# Nu_Multi_Output_Board.net
KiCad netlist of a schematic drawn in EAGLE
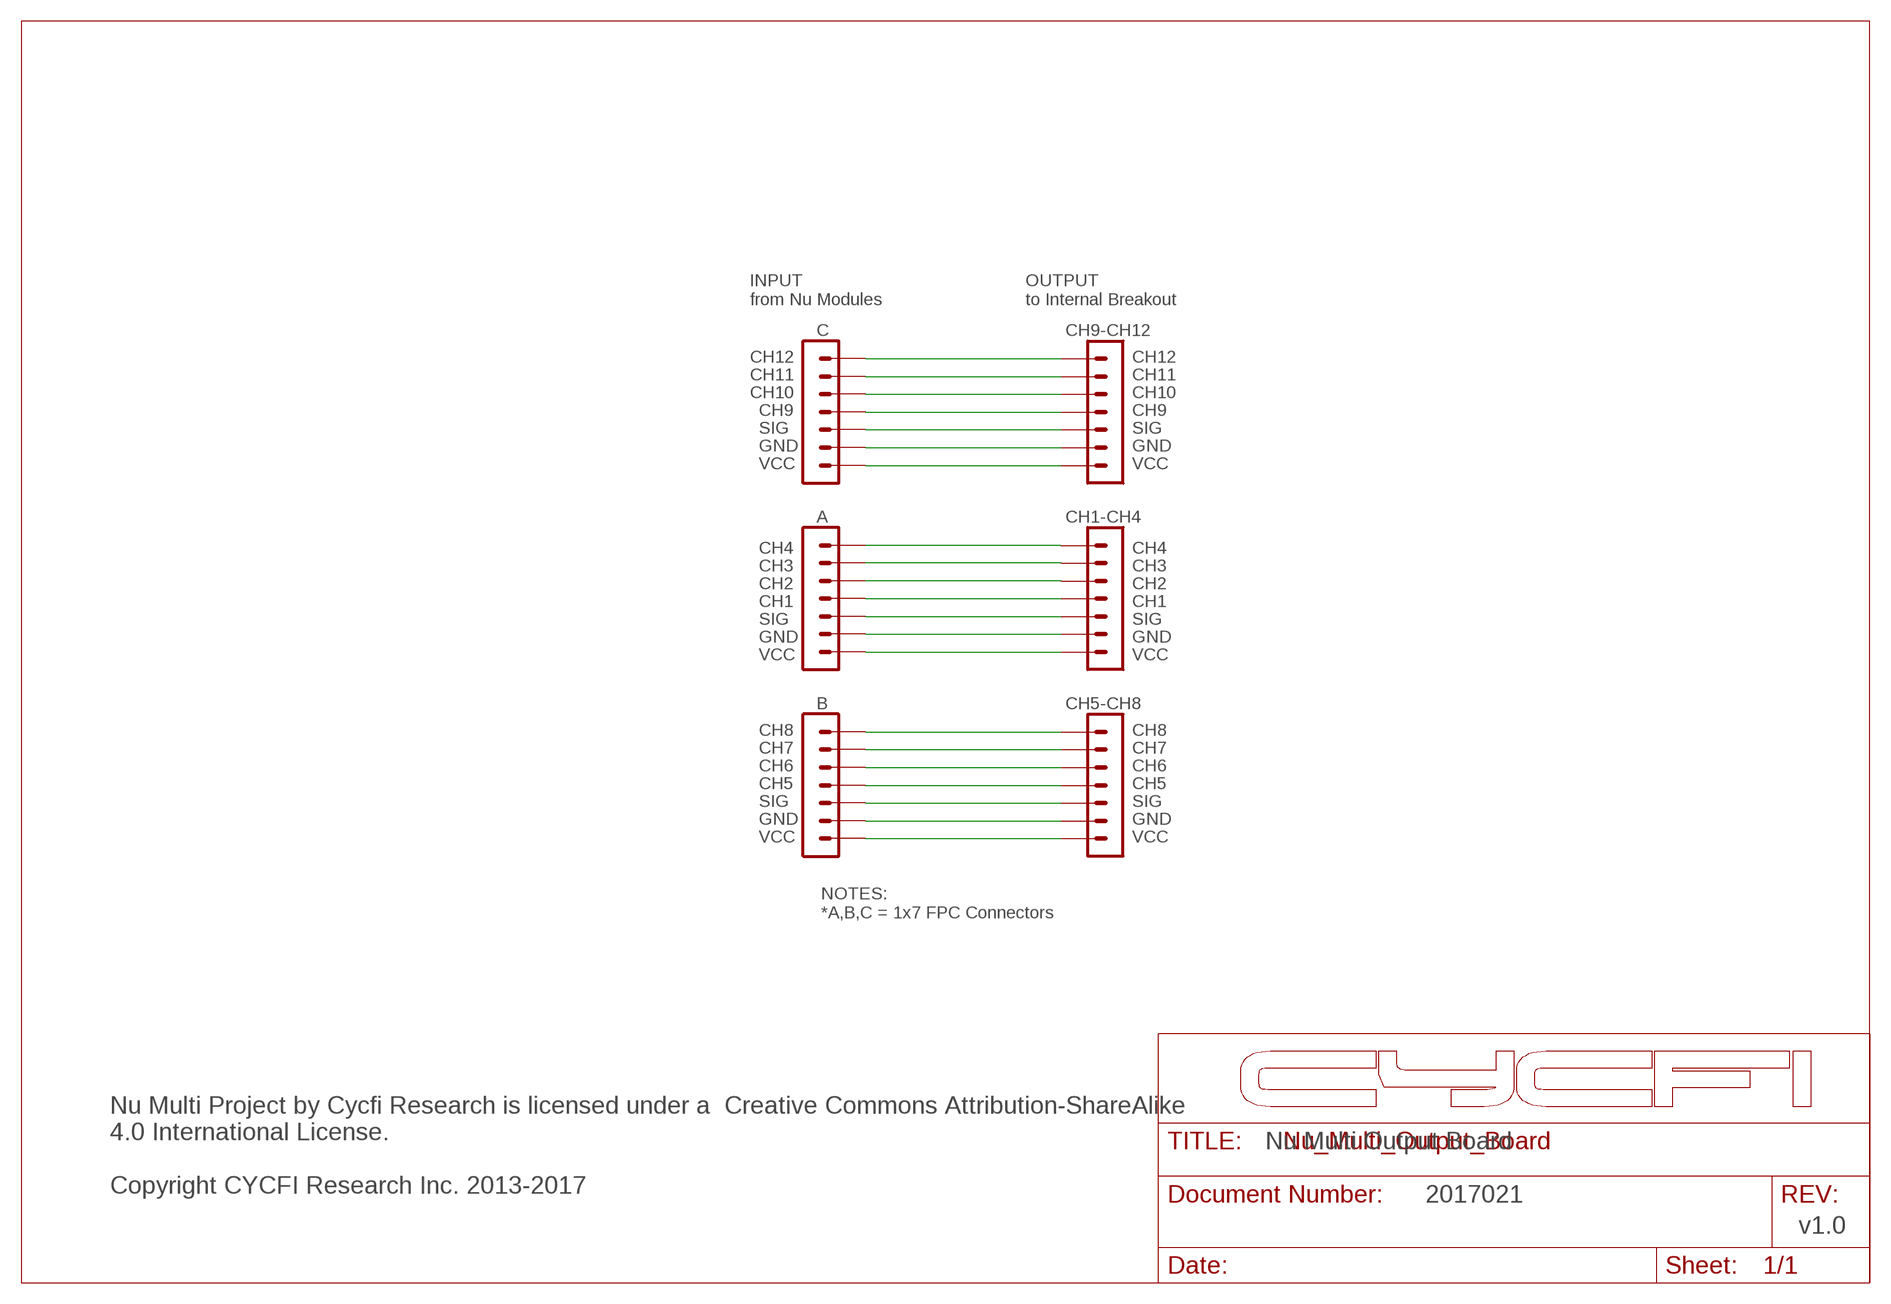
[diagram p0: schematic, sheet 1]

(export (version "E")
  (design (tool "Eeschema 10.0.6"))
  (components
    (comp (ref "H1")
      (value "7P_ZIF_59453-071110EDHLF")
      (footprint "eagle-import:7P_ZIF_59453-071110EDHLF")
      (libsource (lib "eagle-import") (part "7P_ZIF_59453-071110EDHLF"))
    )
    (comp (ref "H2")
      (value "7P_ZIF_59453-071110EDHLF")
      (footprint "eagle-import:7P_ZIF_59453-071110EDHLF")
      (libsource (lib "eagle-import") (part "7P_ZIF_59453-071110EDHLF"))
    )
    (comp (ref "H3")
      (value "7P_ZIF_59453-071110EDHLF")
      (footprint "eagle-import:7P_ZIF_59453-071110EDHLF")
      (libsource (lib "eagle-import") (part "7P_ZIF_59453-071110EDHLF"))
    )
    (comp (ref "H4")
      (value "7P_ZIF_59453-071110EDHLF")
      (footprint "eagle-import:7P_ZIF_59453-071110EDHLF")
      (libsource (lib "eagle-import") (part "7P_ZIF_59453-071110EDHLF"))
    )
    (comp (ref "H5")
      (value "7P_ZIF_59453-071110EDHLF")
      (footprint "eagle-import:7P_ZIF_59453-071110EDHLF")
      (libsource (lib "eagle-import") (part "7P_ZIF_59453-071110EDHLF"))
    )
    (comp (ref "H6")
      (value "7P_ZIF_59453-071110EDHLF")
      (footprint "eagle-import:7P_ZIF_59453-071110EDHLF")
      (libsource (lib "eagle-import") (part "7P_ZIF_59453-071110EDHLF"))
    )
  )
  (nets
    (net (code "1") (name "/GND") (class "Default")
      (node (ref "H1") (pin "P$6") (pinfunction "6_P$6") (pintype "passive"))
      (node (ref "H2") (pin "P$6") (pinfunction "6_P$6") (pintype "passive"))
      (node (ref "H3") (pin "P$6") (pinfunction "6_P$6") (pintype "passive"))
      (node (ref "H4") (pin "P$6") (pinfunction "6_P$6") (pintype "passive"))
      (node (ref "H5") (pin "P$6") (pinfunction "6_P$6") (pintype "passive"))
      (node (ref "H6") (pin "P$6") (pinfunction "6_P$6") (pintype "passive"))
    )
    (net (code "2") (name "Net-(H1-1)") (class "Default")
      (node (ref "H1") (pin "P$1") (pinfunction "1_P$1") (pintype "passive"))
      (node (ref "H3") (pin "P$1") (pinfunction "1_P$1") (pintype "passive"))
    )
    (net (code "3") (name "Net-(H1-2)") (class "Default")
      (node (ref "H1") (pin "P$2") (pinfunction "2_P$2") (pintype "passive"))
      (node (ref "H3") (pin "P$2") (pinfunction "2_P$2") (pintype "passive"))
    )
    (net (code "4") (name "Net-(H1-3)") (class "Default")
      (node (ref "H1") (pin "P$3") (pinfunction "3_P$3") (pintype "passive"))
      (node (ref "H3") (pin "P$3") (pinfunction "3_P$3") (pintype "passive"))
    )
    (net (code "5") (name "Net-(H1-4)") (class "Default")
      (node (ref "H1") (pin "P$4") (pinfunction "4_P$4") (pintype "passive"))
      (node (ref "H3") (pin "P$4") (pinfunction "4_P$4") (pintype "passive"))
    )
    (net (code "6") (name "Net-(H1-5)") (class "Default")
      (node (ref "H1") (pin "P$5") (pinfunction "5_P$5") (pintype "passive"))
      (node (ref "H3") (pin "P$5") (pinfunction "5_P$5") (pintype "passive"))
    )
    (net (code "7") (name "Net-(H1-7)") (class "Default")
      (node (ref "H1") (pin "P$7") (pinfunction "7_P$7") (pintype "passive"))
      (node (ref "H3") (pin "P$7") (pinfunction "7_P$7") (pintype "passive"))
    )
    (net (code "8") (name "Net-(H2-1)") (class "Default")
      (node (ref "H2") (pin "P$1") (pinfunction "1_P$1") (pintype "passive"))
      (node (ref "H4") (pin "P$1") (pinfunction "1_P$1") (pintype "passive"))
    )
    (net (code "9") (name "Net-(H2-2)") (class "Default")
      (node (ref "H2") (pin "P$2") (pinfunction "2_P$2") (pintype "passive"))
      (node (ref "H4") (pin "P$2") (pinfunction "2_P$2") (pintype "passive"))
    )
    (net (code "10") (name "Net-(H2-3)") (class "Default")
      (node (ref "H2") (pin "P$3") (pinfunction "3_P$3") (pintype "passive"))
      (node (ref "H4") (pin "P$3") (pinfunction "3_P$3") (pintype "passive"))
    )
    (net (code "11") (name "Net-(H2-4)") (class "Default")
      (node (ref "H2") (pin "P$4") (pinfunction "4_P$4") (pintype "passive"))
      (node (ref "H4") (pin "P$4") (pinfunction "4_P$4") (pintype "passive"))
    )
    (net (code "12") (name "Net-(H2-5)") (class "Default")
      (node (ref "H2") (pin "P$5") (pinfunction "5_P$5") (pintype "passive"))
      (node (ref "H4") (pin "P$5") (pinfunction "5_P$5") (pintype "passive"))
    )
    (net (code "13") (name "Net-(H2-7)") (class "Default")
      (node (ref "H2") (pin "P$7") (pinfunction "7_P$7") (pintype "passive"))
      (node (ref "H4") (pin "P$7") (pinfunction "7_P$7") (pintype "passive"))
    )
    (net (code "14") (name "Net-(H5-1)") (class "Default")
      (node (ref "H5") (pin "P$1") (pinfunction "1_P$1") (pintype "passive"))
      (node (ref "H6") (pin "P$1") (pinfunction "1_P$1") (pintype "passive"))
    )
    (net (code "15") (name "Net-(H5-2)") (class "Default")
      (node (ref "H5") (pin "P$2") (pinfunction "2_P$2") (pintype "passive"))
      (node (ref "H6") (pin "P$2") (pinfunction "2_P$2") (pintype "passive"))
    )
    (net (code "16") (name "Net-(H5-3)") (class "Default")
      (node (ref "H5") (pin "P$3") (pinfunction "3_P$3") (pintype "passive"))
      (node (ref "H6") (pin "P$3") (pinfunction "3_P$3") (pintype "passive"))
    )
    (net (code "17") (name "Net-(H5-4)") (class "Default")
      (node (ref "H5") (pin "P$4") (pinfunction "4_P$4") (pintype "passive"))
      (node (ref "H6") (pin "P$4") (pinfunction "4_P$4") (pintype "passive"))
    )
    (net (code "18") (name "Net-(H5-5)") (class "Default")
      (node (ref "H5") (pin "P$5") (pinfunction "5_P$5") (pintype "passive"))
      (node (ref "H6") (pin "P$5") (pinfunction "5_P$5") (pintype "passive"))
    )
    (net (code "19") (name "Net-(H5-7)") (class "Default")
      (node (ref "H5") (pin "P$7") (pinfunction "7_P$7") (pintype "passive"))
      (node (ref "H6") (pin "P$7") (pinfunction "7_P$7") (pintype "passive"))
    )
  )
)
